# Sch_Dr_PWM_Out.net
KiCad netlist of a schematic drawn in Altium Designer
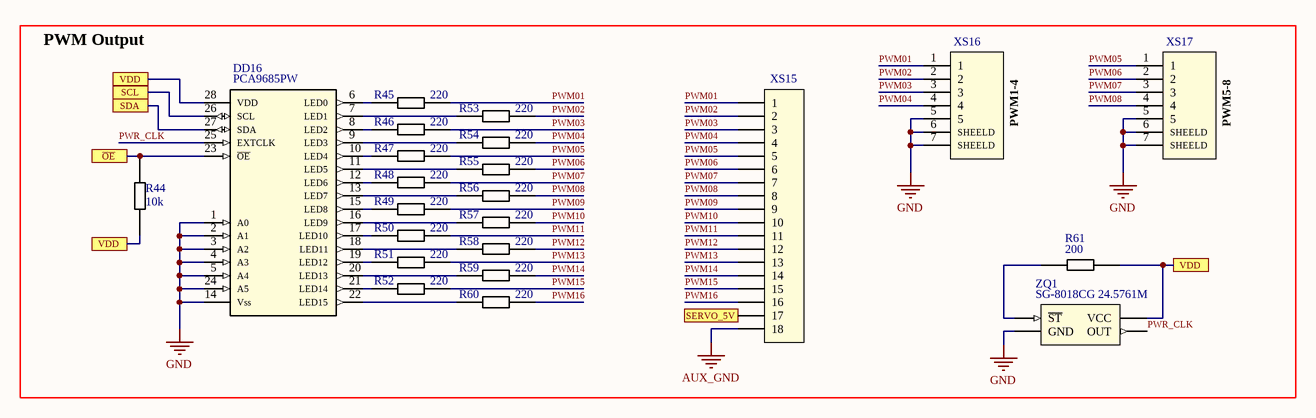
[diagram p0: Sch_Dr_PWM_Out .SchDoc]

(export (version "E")
  (design (tool "Eeschema 10.0.6"))
  (components
    (comp (ref "DD16")
      (value "PCA9685PW")
      (footprint "TSSOP28")
      (description "16-ch, 12-bit PWM Fm+ I2C-bus LED controller")
      (libsource (lib "Dr_lib") (part "PCA9685PW"))
    )
    (comp (ref "R44")
      (value "10k")
      (footprint "Res_0603")
      (description "CR-03FL7---10K")
      (libsource (lib "") (part "Res__1"))
    )
    (comp (ref "R45")
      (value "220")
      (footprint "Res_0603")
      (description "CR-03FL7--220R")
      (libsource (lib "Dr_lib") (part "Res_"))
    )
    (comp (ref "R46")
      (value "220")
      (footprint "Res_0603")
      (description "CR-03FL7--220R")
      (libsource (lib "Dr_lib") (part "Res_"))
    )
    (comp (ref "R47")
      (value "220")
      (footprint "Res_0603")
      (description "CR-03FL7--220R")
      (libsource (lib "Dr_lib") (part "Res_"))
    )
    (comp (ref "R48")
      (value "220")
      (footprint "Res_0603")
      (description "CR-03FL7--220R")
      (libsource (lib "Dr_lib") (part "Res_"))
    )
    (comp (ref "R49")
      (value "220")
      (footprint "Res_0603")
      (description "CR-03FL7--220R")
      (libsource (lib "Dr_lib") (part "Res_"))
    )
    (comp (ref "R50")
      (value "220")
      (footprint "Res_0603")
      (description "CR-03FL7--220R")
      (libsource (lib "Dr_lib") (part "Res_"))
    )
    (comp (ref "R51")
      (value "220")
      (footprint "Res_0603")
      (description "CR-03FL7--220R")
      (libsource (lib "Dr_lib") (part "Res_"))
    )
    (comp (ref "R52")
      (value "220")
      (footprint "Res_0603")
      (description "CR-03FL7--220R")
      (libsource (lib "Dr_lib") (part "Res_"))
    )
    (comp (ref "R53")
      (value "220")
      (footprint "Res_0603")
      (description "CR-03FL7--220R")
      (libsource (lib "Dr_lib") (part "Res_"))
    )
    (comp (ref "R54")
      (value "220")
      (footprint "Res_0603")
      (description "CR-03FL7--220R")
      (libsource (lib "Dr_lib") (part "Res_"))
    )
    (comp (ref "R55")
      (value "220")
      (footprint "Res_0603")
      (description "CR-03FL7--220R")
      (libsource (lib "Dr_lib") (part "Res_"))
    )
    (comp (ref "R56")
      (value "220")
      (footprint "Res_0603")
      (description "CR-03FL7--220R")
      (libsource (lib "Dr_lib") (part "Res_"))
    )
    (comp (ref "R57")
      (value "220")
      (footprint "Res_0603")
      (description "CR-03FL7--220R")
      (libsource (lib "Dr_lib") (part "Res_"))
    )
    (comp (ref "R58")
      (value "220")
      (footprint "Res_0603")
      (description "CR-03FL7--220R")
      (libsource (lib "Dr_lib") (part "Res_"))
    )
    (comp (ref "R59")
      (value "220")
      (footprint "Res_0603")
      (description "CR-03FL7--220R")
      (libsource (lib "Dr_lib") (part "Res_"))
    )
    (comp (ref "R60")
      (value "220")
      (footprint "Res_0603")
      (description "CR-03FL7--220R")
      (libsource (lib "Dr_lib") (part "Res_"))
    )
    (comp (ref "R61")
      (value "200")
      (footprint "Res_0603")
      (description "CR-03FL7--200R")
      (libsource (lib "Dr_lib") (part "Res_"))
    )
    (comp (ref "XS15")
      (value "Servo16x")
      (footprint "Servo16x")
      (description "16*3")
      (libsource (lib "Dr_lib") (part "Servo16x"))
    )
    (comp (ref "XS16")
      (value "BM05B-GHS-TBT(LF)(SN)(N)")
      (footprint "BM05B-GHS-TBT")
      (libsource (lib "Dr_lib") (part "BM05B-GHS-TBT(LF)(SN)(N)"))
    )
    (comp (ref "XS17")
      (value "BM05B-GHS-TBT(LF)(SN)(N)")
      (footprint "BM05B-GHS-TBT")
      (libsource (lib "Dr_lib") (part "BM05B-GHS-TBT(LF)(SN)(N)"))
    )
    (comp (ref "ZQ1")
      (value "SG-8018CG 24.5761M")
      (footprint "SG-8018CG 24.5761M-TJHSA0")
      (description "Crystal Oscillator 24.576MHz")
      (libsource (lib "Dr_lib") (part "SG-8018CG 24.5761M"))
    )
  )
  (nets
    (net (code "1") (name "/PWM01") (class "Default")
      (node (ref "R45") (pin "2") (pinfunction "2_2") (pintype "passive"))
      (node (ref "XS15") (pin "1") (pinfunction "1_1") (pintype "passive"))
      (node (ref "XS16") (pin "1") (pinfunction "1_1") (pintype "passive"))
    )
    (net (code "2") (name "/PWM02") (class "Default")
      (node (ref "R53") (pin "2") (pinfunction "2_2") (pintype "passive"))
      (node (ref "XS15") (pin "2") (pinfunction "2_2") (pintype "passive"))
      (node (ref "XS16") (pin "2") (pinfunction "2_2") (pintype "passive"))
    )
    (net (code "3") (name "/PWM03") (class "Default")
      (node (ref "R46") (pin "2") (pinfunction "2_2") (pintype "passive"))
      (node (ref "XS15") (pin "3") (pinfunction "3_3") (pintype "passive"))
      (node (ref "XS16") (pin "3") (pinfunction "3_3") (pintype "passive"))
    )
    (net (code "4") (name "/PWM04") (class "Default")
      (node (ref "R54") (pin "2") (pinfunction "2_2") (pintype "passive"))
      (node (ref "XS15") (pin "4") (pinfunction "4_4") (pintype "passive"))
      (node (ref "XS16") (pin "4") (pinfunction "4_4") (pintype "passive"))
    )
    (net (code "5") (name "/PWM05") (class "Default")
      (node (ref "R47") (pin "2") (pinfunction "2_2") (pintype "passive"))
      (node (ref "XS15") (pin "5") (pinfunction "5_5") (pintype "passive"))
      (node (ref "XS17") (pin "1") (pinfunction "1_1") (pintype "passive"))
    )
    (net (code "6") (name "/PWM06") (class "Default")
      (node (ref "R55") (pin "2") (pinfunction "2_2") (pintype "passive"))
      (node (ref "XS15") (pin "6") (pinfunction "6_6") (pintype "passive"))
      (node (ref "XS17") (pin "2") (pinfunction "2_2") (pintype "passive"))
    )
    (net (code "7") (name "/PWM07") (class "Default")
      (node (ref "R48") (pin "2") (pinfunction "2_2") (pintype "passive"))
      (node (ref "XS15") (pin "7") (pinfunction "7_7") (pintype "passive"))
      (node (ref "XS17") (pin "3") (pinfunction "3_3") (pintype "passive"))
    )
    (net (code "8") (name "/PWM08") (class "Default")
      (node (ref "R56") (pin "2") (pinfunction "2_2") (pintype "passive"))
      (node (ref "XS15") (pin "8") (pinfunction "8_8") (pintype "passive"))
      (node (ref "XS17") (pin "4") (pinfunction "4_4") (pintype "passive"))
    )
    (net (code "9") (name "/PWM09") (class "Default")
      (node (ref "R49") (pin "2") (pinfunction "2_2") (pintype "passive"))
      (node (ref "XS15") (pin "9") (pinfunction "9_9") (pintype "passive"))
    )
    (net (code "10") (name "/PWM10") (class "Default")
      (node (ref "R57") (pin "2") (pinfunction "2_2") (pintype "passive"))
      (node (ref "XS15") (pin "10") (pinfunction "10_10") (pintype "passive"))
    )
    (net (code "11") (name "/PWM11") (class "Default")
      (node (ref "R50") (pin "2") (pinfunction "2_2") (pintype "passive"))
      (node (ref "XS15") (pin "11") (pinfunction "11_11") (pintype "passive"))
    )
    (net (code "12") (name "/PWM12") (class "Default")
      (node (ref "R58") (pin "2") (pinfunction "2_2") (pintype "passive"))
      (node (ref "XS15") (pin "12") (pinfunction "12_12") (pintype "passive"))
    )
    (net (code "13") (name "/PWM13") (class "Default")
      (node (ref "R51") (pin "2") (pinfunction "2_2") (pintype "passive"))
      (node (ref "XS15") (pin "13") (pinfunction "13_13") (pintype "passive"))
    )
    (net (code "14") (name "/PWM14") (class "Default")
      (node (ref "R59") (pin "2") (pinfunction "2_2") (pintype "passive"))
      (node (ref "XS15") (pin "14") (pinfunction "14_14") (pintype "passive"))
    )
    (net (code "15") (name "/PWM15") (class "Default")
      (node (ref "R52") (pin "2") (pinfunction "2_2") (pintype "passive"))
      (node (ref "XS15") (pin "15") (pinfunction "15_15") (pintype "passive"))
    )
    (net (code "16") (name "/PWM16") (class "Default")
      (node (ref "R60") (pin "2") (pinfunction "2_2") (pintype "passive"))
      (node (ref "XS15") (pin "16") (pinfunction "16_16") (pintype "passive"))
    )
    (net (code "17") (name "/PWR_CLK") (class "Default")
      (node (ref "DD16") (pin "25") (pinfunction "EXTCLK_25") (pintype "input"))
      (node (ref "ZQ1") (pin "3") (pinfunction "OUT_3") (pintype "output"))
    )
    (net (code "18") (name "/SCL") (class "Default")
      (node (ref "DD16") (pin "26") (pinfunction "SCL_26") (pintype "bidirectional"))
    )
    (net (code "19") (name "/SDA") (class "Default")
      (node (ref "DD16") (pin "27") (pinfunction "SDA_27") (pintype "bidirectional"))
    )
    (net (code "20") (name "/SERVO_5V") (class "Default")
      (node (ref "XS15") (pin "17") (pinfunction "17_17") (pintype "passive"))
    )
    (net (code "21") (name "/VDD") (class "Default")
      (node (ref "DD16") (pin "28") (pinfunction "VDD_28") (pintype "passive"))
      (node (ref "R44") (pin "1") (pinfunction "1_1") (pintype "passive"))
      (node (ref "R61") (pin "2") (pinfunction "2_2") (pintype "passive"))
      (node (ref "ZQ1") (pin "4") (pinfunction "VCC_4") (pintype "power_in"))
    )
    (net (code "22") (name "/~{OE}") (class "Default")
      (node (ref "DD16") (pin "23") (pinfunction "~{OE}_23") (pintype "input"))
      (node (ref "R44") (pin "2") (pinfunction "2_2") (pintype "passive"))
    )
    (net (code "23") (name "AUX_GND") (class "Default")
      (node (ref "XS15") (pin "18") (pinfunction "18_18") (pintype "passive"))
    )
    (net (code "24") (name "GND") (class "Default")
      (node (ref "DD16") (pin "1") (pinfunction "A0_1") (pintype "input"))
      (node (ref "DD16") (pin "14") (pinfunction "Vss_14") (pintype "passive"))
      (node (ref "DD16") (pin "2") (pinfunction "A1_2") (pintype "input"))
      (node (ref "DD16") (pin "24") (pinfunction "A5_24") (pintype "input"))
      (node (ref "DD16") (pin "3") (pinfunction "A2_3") (pintype "input"))
      (node (ref "DD16") (pin "4") (pinfunction "A3_4") (pintype "input"))
      (node (ref "DD16") (pin "5") (pinfunction "A4_5") (pintype "input"))
      (node (ref "XS16") (pin "5") (pinfunction "5_5") (pintype "passive"))
      (node (ref "XS16") (pin "6") (pinfunction "SHEELD_6") (pintype "passive"))
      (node (ref "XS16") (pin "7") (pinfunction "SHEELD_7") (pintype "passive"))
      (node (ref "XS17") (pin "5") (pinfunction "5_5") (pintype "passive"))
      (node (ref "XS17") (pin "6") (pinfunction "SHEELD_6") (pintype "passive"))
      (node (ref "XS17") (pin "7") (pinfunction "SHEELD_7") (pintype "passive"))
      (node (ref "ZQ1") (pin "2") (pinfunction "GND_2") (pintype "power_in"))
    )
    (net (code "25") (name "Net-(DD16-LED0)") (class "Default")
      (node (ref "DD16") (pin "6") (pinfunction "LED0_6") (pintype "output"))
      (node (ref "R45") (pin "1") (pinfunction "1_1") (pintype "passive"))
    )
    (net (code "26") (name "Net-(DD16-LED1)") (class "Default")
      (node (ref "DD16") (pin "7") (pinfunction "LED1_7") (pintype "output"))
      (node (ref "R53") (pin "1") (pinfunction "1_1") (pintype "passive"))
    )
    (net (code "27") (name "Net-(DD16-LED2)") (class "Default")
      (node (ref "DD16") (pin "8") (pinfunction "LED2_8") (pintype "output"))
      (node (ref "R46") (pin "1") (pinfunction "1_1") (pintype "passive"))
    )
    (net (code "28") (name "Net-(DD16-LED3)") (class "Default")
      (node (ref "DD16") (pin "9") (pinfunction "LED3_9") (pintype "output"))
      (node (ref "R54") (pin "1") (pinfunction "1_1") (pintype "passive"))
    )
    (net (code "29") (name "Net-(DD16-LED4)") (class "Default")
      (node (ref "DD16") (pin "10") (pinfunction "LED4_10") (pintype "output"))
      (node (ref "R47") (pin "1") (pinfunction "1_1") (pintype "passive"))
    )
    (net (code "30") (name "Net-(DD16-LED5)") (class "Default")
      (node (ref "DD16") (pin "11") (pinfunction "LED5_11") (pintype "output"))
      (node (ref "R55") (pin "1") (pinfunction "1_1") (pintype "passive"))
    )
    (net (code "31") (name "Net-(DD16-LED6)") (class "Default")
      (node (ref "DD16") (pin "12") (pinfunction "LED6_12") (pintype "output"))
      (node (ref "R48") (pin "1") (pinfunction "1_1") (pintype "passive"))
    )
    (net (code "32") (name "Net-(DD16-LED7)") (class "Default")
      (node (ref "DD16") (pin "13") (pinfunction "LED7_13") (pintype "output"))
      (node (ref "R56") (pin "1") (pinfunction "1_1") (pintype "passive"))
    )
    (net (code "33") (name "Net-(DD16-LED8)") (class "Default")
      (node (ref "DD16") (pin "15") (pinfunction "LED8_15") (pintype "output"))
      (node (ref "R49") (pin "1") (pinfunction "1_1") (pintype "passive"))
    )
    (net (code "34") (name "Net-(DD16-LED9)") (class "Default")
      (node (ref "DD16") (pin "16") (pinfunction "LED9_16") (pintype "output"))
      (node (ref "R57") (pin "1") (pinfunction "1_1") (pintype "passive"))
    )
    (net (code "35") (name "Net-(DD16-LED10)") (class "Default")
      (node (ref "DD16") (pin "17") (pinfunction "LED10_17") (pintype "output"))
      (node (ref "R50") (pin "1") (pinfunction "1_1") (pintype "passive"))
    )
    (net (code "36") (name "Net-(DD16-LED11)") (class "Default")
      (node (ref "DD16") (pin "18") (pinfunction "LED11_18") (pintype "output"))
      (node (ref "R58") (pin "1") (pinfunction "1_1") (pintype "passive"))
    )
    (net (code "37") (name "Net-(DD16-LED12)") (class "Default")
      (node (ref "DD16") (pin "19") (pinfunction "LED12_19") (pintype "output"))
      (node (ref "R51") (pin "1") (pinfunction "1_1") (pintype "passive"))
    )
    (net (code "38") (name "Net-(DD16-LED13)") (class "Default")
      (node (ref "DD16") (pin "20") (pinfunction "LED13_20") (pintype "output"))
      (node (ref "R59") (pin "1") (pinfunction "1_1") (pintype "passive"))
    )
    (net (code "39") (name "Net-(DD16-LED14)") (class "Default")
      (node (ref "DD16") (pin "21") (pinfunction "LED14_21") (pintype "output"))
      (node (ref "R52") (pin "1") (pinfunction "1_1") (pintype "passive"))
    )
    (net (code "40") (name "Net-(DD16-LED15)") (class "Default")
      (node (ref "DD16") (pin "22") (pinfunction "LED15_22") (pintype "output"))
      (node (ref "R60") (pin "1") (pinfunction "1_1") (pintype "passive"))
    )
    (net (code "41") (name "Net-(ZQ1-~{ST})") (class "Default")
      (node (ref "R61") (pin "1") (pinfunction "1_1") (pintype "passive"))
      (node (ref "ZQ1") (pin "1") (pinfunction "~{ST}_1") (pintype "input"))
    )
  )
)
